# 18_-SP3_PMIC_BLOCK.net
KiCad netlist of a schematic drawn in Altium Designer
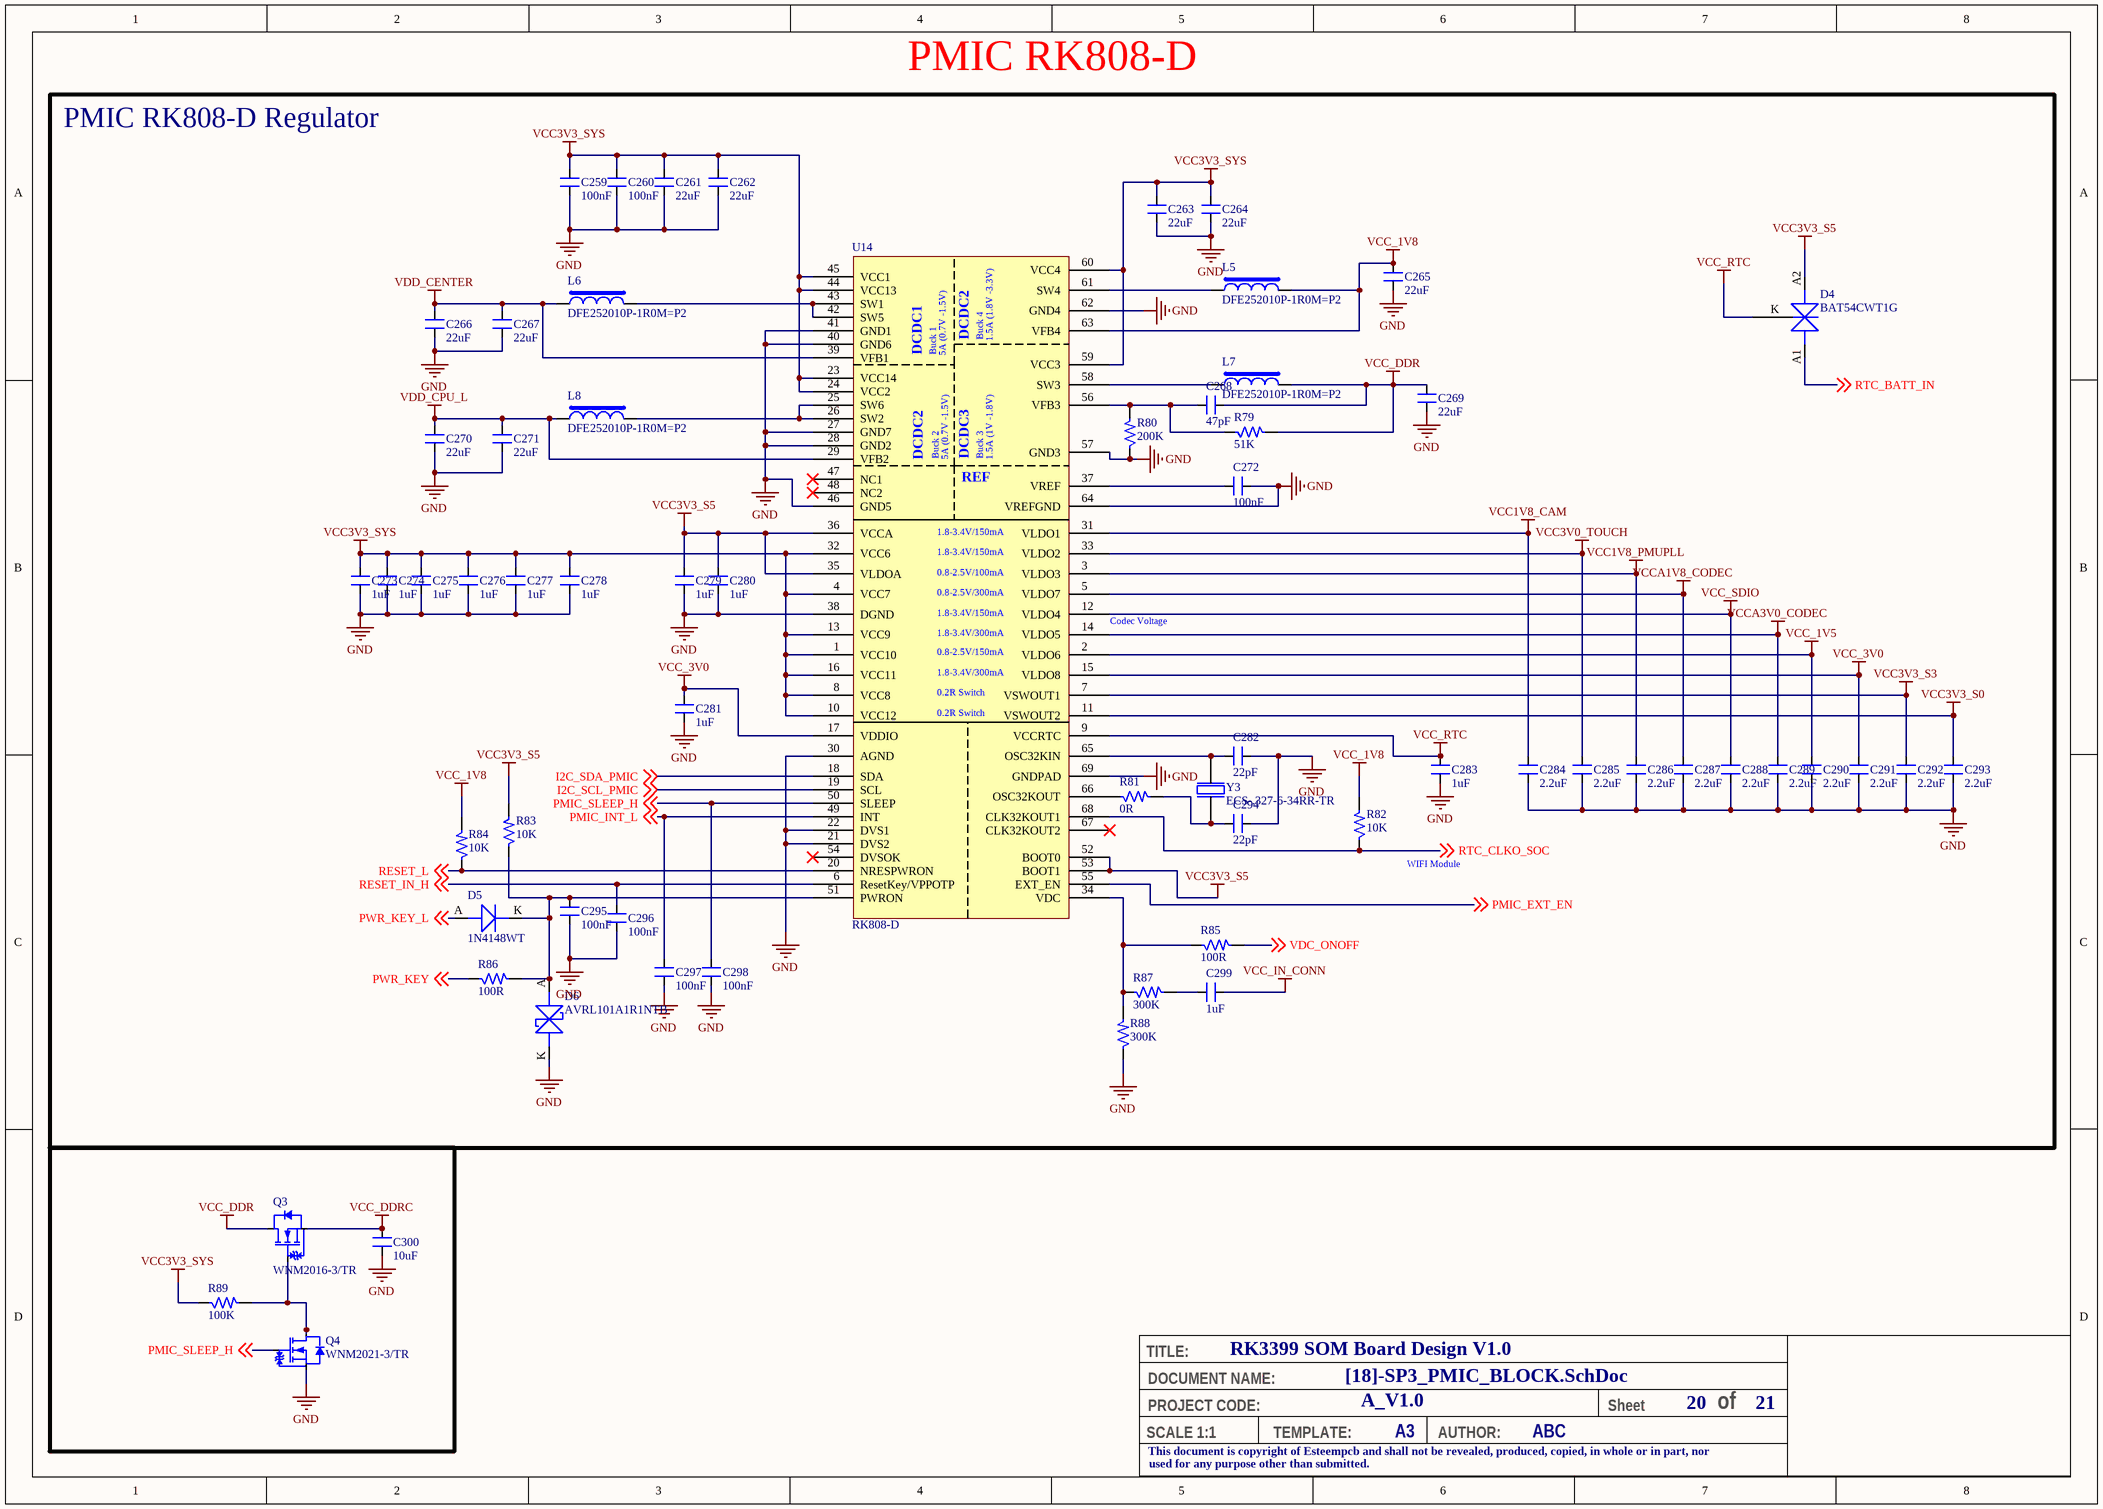
[diagram p0: [18]-SP3_PMIC_BLOCK.SchDoc]

(export (version "E")
  (design (tool "Eeschema 10.0.6"))
  (components
    (comp (ref "C259")
      (value "100nF")
      (footprint "CAP_0402")
      (description "0.1µF ±10% 25V Ceramic Capacitor X7R 0402 (1005 Metric)")
      (fields
        (field (name "MANUFACTURER") "Walsin Technology Corporation")
        (field (name "MANUFACTURER PART NUMBER") "0402B104K250CT")
      )
      (libsource (lib "RK3399 _Module_Schlib") (part "CAP_100nF-25V-10%-0402"))
    )
    (comp (ref "C260")
      (value "100nF")
      (footprint "CAP_0402")
      (description "0.1µF ±10% 25V Ceramic Capacitor X7R 0402 (1005 Metric)")
      (fields
        (field (name "MANUFACTURER") "Walsin Technology Corporation")
        (field (name "MANUFACTURER PART NUMBER") "0402B104K250CT")
      )
      (libsource (lib "RK3399 _Module_Schlib") (part "CAP_100nF-25V-10%-0402"))
    )
    (comp (ref "C261")
      (value "22uF")
      (footprint "CAP_0603")
      (description "22µF ±20% 10V Ceramic Capacitor X5R 0603 (1608 Metric)")
      (fields
        (field (name "MANUFACTURER") "Murata Electronics")
        (field (name "MANUFACTURER PART NUMBER") "GRM188R61A226ME15D")
      )
      (libsource (lib "RK3399 _Module_Schlib") (part "CAP_22uF-10V-20%-0603"))
    )
    (comp (ref "C262")
      (value "22uF")
      (footprint "CAP_0603")
      (description "22µF ±20% 10V Ceramic Capacitor X5R 0603 (1608 Metric)")
      (fields
        (field (name "MANUFACTURER") "Murata Electronics")
        (field (name "MANUFACTURER PART NUMBER") "GRM188R61A226ME15D")
      )
      (libsource (lib "RK3399 _Module_Schlib") (part "CAP_22uF-10V-20%-0603"))
    )
    (comp (ref "C263")
      (value "22uF")
      (footprint "CAP_0603")
      (description "22µF ±20% 10V Ceramic Capacitor X5R 0603 (1608 Metric)")
      (fields
        (field (name "MANUFACTURER") "Murata Electronics")
        (field (name "MANUFACTURER PART NUMBER") "GRM188R61A226ME15D")
      )
      (libsource (lib "RK3399 _Module_Schlib") (part "CAP_22uF-10V-20%-0603"))
    )
    (comp (ref "C264")
      (value "22uF")
      (footprint "CAP_0603")
      (description "22µF ±20% 10V Ceramic Capacitor X5R 0603 (1608 Metric)")
      (fields
        (field (name "MANUFACTURER") "Murata Electronics")
        (field (name "MANUFACTURER PART NUMBER") "GRM188R61A226ME15D")
      )
      (libsource (lib "RK3399 _Module_Schlib") (part "CAP_22uF-10V-20%-0603"))
    )
    (comp (ref "C265")
      (value "22uF")
      (footprint "CAP_0603")
      (description "22µF ±20% 10V Ceramic Capacitor X5R 0603 (1608 Metric)")
      (fields
        (field (name "MANUFACTURER") "Murata Electronics")
        (field (name "MANUFACTURER PART NUMBER") "GRM188R61A226ME15D")
      )
      (libsource (lib "RK3399 _Module_Schlib") (part "CAP_22uF-10V-20%-0603"))
    )
    (comp (ref "C266")
      (value "22uF")
      (footprint "CAP_0603")
      (description "22µF ±20% 10V Ceramic Capacitor X5R 0603 (1608 Metric)")
      (fields
        (field (name "MANUFACTURER") "Murata Electronics")
        (field (name "MANUFACTURER PART NUMBER") "GRM188R61A226ME15D")
      )
      (libsource (lib "RK3399 _Module_Schlib") (part "CAP_22uF-10V-20%-0603"))
    )
    (comp (ref "C267")
      (value "22uF")
      (footprint "CAP_0603")
      (description "22µF ±20% 10V Ceramic Capacitor X5R 0603 (1608 Metric)")
      (fields
        (field (name "MANUFACTURER") "Murata Electronics")
        (field (name "MANUFACTURER PART NUMBER") "GRM188R61A226ME15D")
      )
      (libsource (lib "RK3399 _Module_Schlib") (part "CAP_22uF-10V-20%-0603"))
    )
    (comp (ref "C268")
      (value "47pF")
      (footprint "CAP_0402")
      (description "47pF ±10% 10V Ceramic Capacitor C0G, NP0 0402 (1005 Metric)")
      (fields
        (field (name "MANUFACTURER") "KEMET")
        (field (name "MANUFACTURER PART NUMBER") "C0402C470K8GAC7867")
      )
      (libsource (lib "RK3399 _Module_Schlib") (part "CAP_47pF-10V-10%-0402"))
    )
    (comp (ref "C269")
      (value "22uF")
      (footprint "CAP_0603")
      (description "22µF ±20% 10V Ceramic Capacitor X5R 0603 (1608 Metric)")
      (fields
        (field (name "MANUFACTURER") "Murata Electronics")
        (field (name "MANUFACTURER PART NUMBER") "GRM188R61A226ME15D")
      )
      (libsource (lib "RK3399 _Module_Schlib") (part "CAP_22uF-10V-20%-0603"))
    )
    (comp (ref "C270")
      (value "22uF")
      (footprint "CAP_0603")
      (description "22µF ±20% 10V Ceramic Capacitor X5R 0603 (1608 Metric)")
      (fields
        (field (name "MANUFACTURER") "Murata Electronics")
        (field (name "MANUFACTURER PART NUMBER") "GRM188R61A226ME15D")
      )
      (libsource (lib "RK3399 _Module_Schlib") (part "CAP_22uF-10V-20%-0603"))
    )
    (comp (ref "C271")
      (value "22uF")
      (footprint "CAP_0603")
      (description "22µF ±20% 10V Ceramic Capacitor X5R 0603 (1608 Metric)")
      (fields
        (field (name "MANUFACTURER") "Murata Electronics")
        (field (name "MANUFACTURER PART NUMBER") "GRM188R61A226ME15D")
      )
      (libsource (lib "RK3399 _Module_Schlib") (part "CAP_22uF-10V-20%-0603"))
    )
    (comp (ref "C272")
      (value "100nF")
      (footprint "CAP_0402")
      (description "0.1µF ±10% 25V Ceramic Capacitor X7R 0402 (1005 Metric)")
      (fields
        (field (name "MANUFACTURER") "Walsin Technology Corporation")
        (field (name "MANUFACTURER PART NUMBER") "0402B104K250CT")
      )
      (libsource (lib "RK3399 _Module_Schlib") (part "CAP_100nF-25V-10%-0402"))
    )
    (comp (ref "C273")
      (value "1uF")
      (footprint "CAP_0402")
      (description "1µF ±10% 16V Ceramic Capacitor X5R 0402 (1005 Metric)")
      (fields
        (field (name "MANUFACTURER") "Knowles Novacap")
        (field (name "MANUFACTURER PART NUMBER") "0402BW105K160YT")
      )
      (libsource (lib "RK3399 _Module_Schlib") (part "CAP_1uF-16V-10%-0402"))
    )
    (comp (ref "C274")
      (value "1uF")
      (footprint "CAP_0402")
      (description "1µF ±10% 16V Ceramic Capacitor X5R 0402 (1005 Metric)")
      (fields
        (field (name "MANUFACTURER") "Knowles Novacap")
        (field (name "MANUFACTURER PART NUMBER") "0402BW105K160YT")
      )
      (libsource (lib "RK3399 _Module_Schlib") (part "CAP_1uF-16V-10%-0402"))
    )
    (comp (ref "C275")
      (value "1uF")
      (footprint "CAP_0402")
      (description "1µF ±10% 16V Ceramic Capacitor X5R 0402 (1005 Metric)")
      (fields
        (field (name "MANUFACTURER") "Knowles Novacap")
        (field (name "MANUFACTURER PART NUMBER") "0402BW105K160YT")
      )
      (libsource (lib "RK3399 _Module_Schlib") (part "CAP_1uF-16V-10%-0402"))
    )
    (comp (ref "C276")
      (value "1uF")
      (footprint "CAP_0402")
      (description "1µF ±10% 16V Ceramic Capacitor X5R 0402 (1005 Metric)")
      (fields
        (field (name "MANUFACTURER") "Knowles Novacap")
        (field (name "MANUFACTURER PART NUMBER") "0402BW105K160YT")
      )
      (libsource (lib "RK3399 _Module_Schlib") (part "CAP_1uF-16V-10%-0402"))
    )
    (comp (ref "C277")
      (value "1uF")
      (footprint "CAP_0402")
      (description "1µF ±10% 16V Ceramic Capacitor X5R 0402 (1005 Metric)")
      (fields
        (field (name "MANUFACTURER") "Knowles Novacap")
        (field (name "MANUFACTURER PART NUMBER") "0402BW105K160YT")
      )
      (libsource (lib "RK3399 _Module_Schlib") (part "CAP_1uF-16V-10%-0402"))
    )
    (comp (ref "C278")
      (value "1uF")
      (footprint "CAP_0402")
      (description "1µF ±10% 16V Ceramic Capacitor X5R 0402 (1005 Metric)")
      (fields
        (field (name "MANUFACTURER") "Knowles Novacap")
        (field (name "MANUFACTURER PART NUMBER") "0402BW105K160YT")
      )
      (libsource (lib "RK3399 _Module_Schlib") (part "CAP_1uF-16V-10%-0402"))
    )
    (comp (ref "C279")
      (value "1uF")
      (footprint "CAP_0402")
      (description "1µF ±10% 16V Ceramic Capacitor X5R 0402 (1005 Metric)")
      (fields
        (field (name "MANUFACTURER") "Knowles Novacap")
        (field (name "MANUFACTURER PART NUMBER") "0402BW105K160YT")
      )
      (libsource (lib "RK3399 _Module_Schlib") (part "CAP_1uF-16V-10%-0402"))
    )
    (comp (ref "C280")
      (value "1uF")
      (footprint "CAP_0402")
      (description "1µF ±10% 16V Ceramic Capacitor X5R 0402 (1005 Metric)")
      (fields
        (field (name "MANUFACTURER") "Knowles Novacap")
        (field (name "MANUFACTURER PART NUMBER") "0402BW105K160YT")
      )
      (libsource (lib "RK3399 _Module_Schlib") (part "CAP_1uF-16V-10%-0402"))
    )
    (comp (ref "C281")
      (value "1uF")
      (footprint "CAP_0402")
      (description "1µF ±10% 16V Ceramic Capacitor X5R 0402 (1005 Metric)")
      (fields
        (field (name "MANUFACTURER") "Knowles Novacap")
        (field (name "MANUFACTURER PART NUMBER") "0402BW105K160YT")
      )
      (libsource (lib "RK3399 _Module_Schlib") (part "CAP_1uF-16V-10%-0402"))
    )
    (comp (ref "C282")
      (value "22pF")
      (footprint "CAP_0402")
      (description "22pF ±10% 10V Ceramic Capacitor C0G, NP0 0402 (1005 Metric)")
      (fields
        (field (name "MANUFACTURER") "KEMET")
        (field (name "MANUFACTURER PART NUMBER") "C0402C220K8GACTU")
      )
      (libsource (lib "RK3399 _Module_Schlib") (part "CAP_22pF-10V-10%-0402"))
    )
    (comp (ref "C283")
      (value "1uF")
      (footprint "CAP_0402")
      (description "1µF ±10% 16V Ceramic Capacitor X5R 0402 (1005 Metric)")
      (fields
        (field (name "MANUFACTURER") "Knowles Novacap")
        (field (name "MANUFACTURER PART NUMBER") "0402BW105K160YT")
      )
      (libsource (lib "RK3399 _Module_Schlib") (part "CAP_1uF-16V-10%-0402"))
    )
    (comp (ref "C284")
      (value "2.2uF")
      (footprint "CAP_0402")
      (description "2.2µF ±10% 10V Ceramic Capacitor X5R 0402 (1005 Metric)")
      (fields
        (field (name "MANUFACTURER") "Murata Electronics")
        (field (name "MANUFACTURER PART NUMBER") "GRM155R61A225KE95D")
      )
      (libsource (lib "RK3399 _Module_Schlib") (part "CAP_2.2uF-10V-10%-0402"))
    )
    (comp (ref "C285")
      (value "2.2uF")
      (footprint "CAP_0402")
      (description "2.2µF ±10% 10V Ceramic Capacitor X5R 0402 (1005 Metric)")
      (fields
        (field (name "MANUFACTURER") "Murata Electronics")
        (field (name "MANUFACTURER PART NUMBER") "GRM155R61A225KE95D")
      )
      (libsource (lib "RK3399 _Module_Schlib") (part "CAP_2.2uF-10V-10%-0402"))
    )
    (comp (ref "C286")
      (value "2.2uF")
      (footprint "CAP_0402")
      (description "2.2µF ±10% 10V Ceramic Capacitor X5R 0402 (1005 Metric)")
      (fields
        (field (name "MANUFACTURER") "Murata Electronics")
        (field (name "MANUFACTURER PART NUMBER") "GRM155R61A225KE95D")
      )
      (libsource (lib "RK3399 _Module_Schlib") (part "CAP_2.2uF-10V-10%-0402"))
    )
    (comp (ref "C287")
      (value "2.2uF")
      (footprint "CAP_0402")
      (description "2.2µF ±10% 10V Ceramic Capacitor X5R 0402 (1005 Metric)")
      (fields
        (field (name "MANUFACTURER") "Murata Electronics")
        (field (name "MANUFACTURER PART NUMBER") "GRM155R61A225KE95D")
      )
      (libsource (lib "RK3399 _Module_Schlib") (part "CAP_2.2uF-10V-10%-0402"))
    )
    (comp (ref "C288")
      (value "2.2uF")
      (footprint "CAP_0402")
      (description "2.2µF ±10% 10V Ceramic Capacitor X5R 0402 (1005 Metric)")
      (fields
        (field (name "MANUFACTURER") "Murata Electronics")
        (field (name "MANUFACTURER PART NUMBER") "GRM155R61A225KE95D")
      )
      (libsource (lib "RK3399 _Module_Schlib") (part "CAP_2.2uF-10V-10%-0402"))
    )
    (comp (ref "C289")
      (value "2.2uF")
      (footprint "CAP_0402")
      (description "2.2µF ±10% 10V Ceramic Capacitor X5R 0402 (1005 Metric)")
      (fields
        (field (name "MANUFACTURER") "Murata Electronics")
        (field (name "MANUFACTURER PART NUMBER") "GRM155R61A225KE95D")
      )
      (libsource (lib "RK3399 _Module_Schlib") (part "CAP_2.2uF-10V-10%-0402"))
    )
    (comp (ref "C290")
      (value "2.2uF")
      (footprint "CAP_0402")
      (description "2.2µF ±10% 10V Ceramic Capacitor X5R 0402 (1005 Metric)")
      (fields
        (field (name "MANUFACTURER") "Murata Electronics")
        (field (name "MANUFACTURER PART NUMBER") "GRM155R61A225KE95D")
      )
      (libsource (lib "RK3399 _Module_Schlib") (part "CAP_2.2uF-10V-10%-0402"))
    )
    (comp (ref "C291")
      (value "2.2uF")
      (footprint "CAP_0402")
      (description "2.2µF ±10% 10V Ceramic Capacitor X5R 0402 (1005 Metric)")
      (fields
        (field (name "MANUFACTURER") "Murata Electronics")
        (field (name "MANUFACTURER PART NUMBER") "GRM155R61A225KE95D")
      )
      (libsource (lib "RK3399 _Module_Schlib") (part "CAP_2.2uF-10V-10%-0402"))
    )
    (comp (ref "C292")
      (value "2.2uF")
      (footprint "CAP_0402")
      (description "2.2µF ±10% 10V Ceramic Capacitor X5R 0402 (1005 Metric)")
      (fields
        (field (name "MANUFACTURER") "Murata Electronics")
        (field (name "MANUFACTURER PART NUMBER") "GRM155R61A225KE95D")
      )
      (libsource (lib "RK3399 _Module_Schlib") (part "CAP_2.2uF-10V-10%-0402"))
    )
    (comp (ref "C293")
      (value "2.2uF")
      (footprint "CAP_0402")
      (description "2.2µF ±10% 10V Ceramic Capacitor X5R 0402 (1005 Metric)")
      (fields
        (field (name "MANUFACTURER") "Murata Electronics")
        (field (name "MANUFACTURER PART NUMBER") "GRM155R61A225KE95D")
      )
      (libsource (lib "RK3399 _Module_Schlib") (part "CAP_2.2uF-10V-10%-0402"))
    )
    (comp (ref "C294")
      (value "22pF")
      (footprint "CAP_0402")
      (description "22pF ±10% 10V Ceramic Capacitor C0G, NP0 0402 (1005 Metric)")
      (fields
        (field (name "MANUFACTURER") "KEMET")
        (field (name "MANUFACTURER PART NUMBER") "C0402C220K8GACTU")
      )
      (libsource (lib "RK3399 _Module_Schlib") (part "CAP_22pF-10V-10%-0402"))
    )
    (comp (ref "C295")
      (value "100nF")
      (footprint "CAP_0402")
      (description "0.1µF ±10% 25V Ceramic Capacitor X7R 0402 (1005 Metric)")
      (fields
        (field (name "MANUFACTURER") "Walsin Technology Corporation")
        (field (name "MANUFACTURER PART NUMBER") "0402B104K250CT")
      )
      (libsource (lib "RK3399 _Module_Schlib") (part "CAP_100nF-25V-10%-0402"))
    )
    (comp (ref "C296")
      (value "100nF")
      (footprint "CAP_0402")
      (description "0.1µF ±10% 25V Ceramic Capacitor X7R 0402 (1005 Metric)")
      (fields
        (field (name "MANUFACTURER") "Walsin Technology Corporation")
        (field (name "MANUFACTURER PART NUMBER") "0402B104K250CT")
      )
      (libsource (lib "RK3399 _Module_Schlib") (part "CAP_100nF-25V-10%-0402"))
    )
    (comp (ref "C297")
      (value "100nF")
      (footprint "CAP_0402")
      (description "0.1µF ±10% 25V Ceramic Capacitor X7R 0402 (1005 Metric)")
      (fields
        (field (name "MANUFACTURER") "Walsin Technology Corporation")
        (field (name "MANUFACTURER PART NUMBER") "0402B104K250CT")
      )
      (libsource (lib "RK3399 _Module_Schlib") (part "CAP_100nF-25V-10%-0402"))
    )
    (comp (ref "C298")
      (value "100nF")
      (footprint "CAP_0402")
      (description "0.1µF ±10% 25V Ceramic Capacitor X7R 0402 (1005 Metric)")
      (fields
        (field (name "MANUFACTURER") "Walsin Technology Corporation")
        (field (name "MANUFACTURER PART NUMBER") "0402B104K250CT")
      )
      (libsource (lib "RK3399 _Module_Schlib") (part "CAP_100nF-25V-10%-0402"))
    )
    (comp (ref "C299")
      (value "1uF")
      (footprint "CAP_0402")
      (description "1µF ±10% 16V Ceramic Capacitor X5R 0402 (1005 Metric)")
      (fields
        (field (name "MANUFACTURER") "Knowles Novacap")
        (field (name "MANUFACTURER PART NUMBER") "0402BW105K160YT")
      )
      (libsource (lib "RK3399 _Module_Schlib") (part "CAP_1uF-16V-10%-0402"))
    )
    (comp (ref "C300")
      (value "10uF")
      (footprint "CAP_0402")
      (description "10µF ±20% 10V Ceramic Capacitor X5R 0402 (1005 Metric)")
      (fields
        (field (name "MANUFACTURER PART NUMBER") "CL05A106MP5NUNC")
        (field (name "MANUFACTURER") "Samsung Electro-Mechanics")
      )
      (libsource (lib "RK3399 _Module_Schlib") (part "CAP_10uF-10V-20%-0402"))
    )
    (comp (ref "D4")
      (value "BAT54CWT1G")
      (footprint "DIO_SOT-323-3")
      (description "Diode Array 1 Pair Common Cathode Schottky 30V 200mA (DC) Surface Mount SC-70, SOT-323")
      (fields (field (name "MANUFACTURER") "ON Semiconductor"))
      (libsource (lib "RK3399 _Module_Schlib") (part "DIO-S-A_30V-200mA-SOT-323"))
    )
    (comp (ref "D5")
      (value "1N4148WT")
      (footprint "DIO_SOD523")
      (description "Diode Standard 100V 300mA (DC) Surface Mount SOD-123")
      (fields (field (name "MANUFACTURER") "FAIRCHILD"))
      (libsource (lib "RK3399 _Module_Schlib") (part "DIO_75V-200mA-SOD-523F"))
    )
    (comp (ref "D6")
      (value "AVRL101A1R1NTB")
      (footprint "DIO_0402_SMD")
      (description "39V Varistor 1 Circuit Surface Mount, MLCV 0402 (1005 Metric)")
      (fields (field (name "MANUFACTURER") "TDK Corporation"))
      (libsource (lib "RK3399 _Module_Schlib") (part "DIO-T_10V-39V-0402"))
    )
    (comp (ref "L5")
      (value "DFE252010P-1R0M=P2")
      (footprint "IND_1008")
      (description "1µH Shielded Wirewound Inductor 3.8A 54mOhm Max 1008 (2520 Metric)")
      (fields (field (name "MANUFACTURER") "Murata Electronics"))
      (libsource (lib "RK3399 _Module_Schlib") (part "IND_1uH-3.8A-20%-1008"))
    )
    (comp (ref "L6")
      (value "DFE252010P-1R0M=P2")
      (footprint "IND_1008")
      (description "1µH Shielded Wirewound Inductor 3.8A 54mOhm Max 1008 (2520 Metric)")
      (fields (field (name "MANUFACTURER") "Murata Electronics"))
      (libsource (lib "RK3399 _Module_Schlib") (part "IND_1uH-3.8A-20%-1008"))
    )
    (comp (ref "L7")
      (value "DFE252010P-1R0M=P2")
      (footprint "IND_1008")
      (description "1µH Shielded Wirewound Inductor 3.8A 54mOhm Max 1008 (2520 Metric)")
      (fields (field (name "MANUFACTURER") "Murata Electronics"))
      (libsource (lib "RK3399 _Module_Schlib") (part "IND_1uH-3.8A-20%-1008"))
    )
    (comp (ref "L8")
      (value "DFE252010P-1R0M=P2")
      (footprint "IND_1008")
      (description "1µH Shielded Wirewound Inductor 3.8A 54mOhm Max 1008 (2520 Metric)")
      (fields (field (name "MANUFACTURER") "Murata Electronics"))
      (libsource (lib "RK3399 _Module_Schlib") (part "IND_1uH-3.8A-20%-1008"))
    )
    (comp (ref "Q3")
      (value "WNM2016-3/TR")
      (footprint "SOT 23-3")
      (description "N Channel 20V 2.9A 1V @ 250uA 47mΩ @ 3.6A,4.5V 700mW SOT-23(SOT-23-3) MOSFET RoHS")
      (fields (field (name "MANUFACTURER") "WILLSEMI(Will Semicon)"))
      (libsource (lib "RK3399 _Module_Schlib") (part "MOSFET-N_20V-2.9A-SOT-23"))
    )
    (comp (ref "Q4")
      (value "WNM2021-3/TR")
      (footprint "SOT-323-3")
      (description "N Channel 20V 820mA 850mV @ 250uA 310mΩ @ 550mA,4.5V 310mW SOT-323(SC-70) MOSFET RoHS")
      (fields (field (name "MANUFACTURER") "WILLSEMI(Will Semicon)"))
      (libsource (lib "RK3399 _Module_Schlib") (part "MOSFET-N_20V-820mA-SOT-323"))
    )
    (comp (ref "R79")
      (value "51K")
      (footprint "RES_0402")
      (description "51 kOhms ±1% 0.1W, 1/10W Chip Resistor 0402 (1005 Metric) Automotive AEC-Q200 Thick Film")
      (fields
        (field (name "MANUFACTURER") "Panasonic Electronic Components")
        (field (name "MANUFACTURER PART NUMBER") "ERJ-2RKF5102X")
      )
      (libsource (lib "RK3399 _Module_Schlib") (part "RES_51K-0.1W-1%-0402"))
    )
    (comp (ref "R80")
      (value "200K")
      (footprint "RES_0402")
      (description "200 kOhms ±1% 0.1W, 1/10W Chip Resistor 0402 (1005 Metric) Automotive AEC-Q200 Thick Film")
      (fields
        (field (name "MANUFACTURER") "Panasonic Electronic Components")
        (field (name "MANUFACTURER PART NUMBER") "ERJ-2RKF2003X")
      )
      (libsource (lib "RK3399 _Module_Schlib") (part "RES_200K-0.1W-1%-0402"))
    )
    (comp (ref "R81")
      (value "0R")
      (footprint "RES_0402")
      (description "0 Ohms Jumper 0.1W, 1/10W Chip Resistor 0402 (1005 Metric) Automotive AEC-Q200 Thick Film")
      (fields
        (field (name "MANUFACTURER") "Panasonic Electronic Components")
        (field (name "MANUFACTURER PART NUMBER") "ERJ-2GE0R00X")
      )
      (libsource (lib "RK3399 _Module_Schlib") (part "RES_0R-0.1W-1%-0402"))
    )
    (comp (ref "R82")
      (value "10K")
      (footprint "RES_0402")
      (description "10 kOhms ±1% 0.1W, 1/10W Chip Resistor 0402 (1005 Metric) Anti-Sulfur Thin Film")
      (fields
        (field (name "MANUFACTURER") "Vishay Beyschlag/Draloric/BC Components")
        (field (name "MANUFACTURER PART NUMBER") "MCS04020C1002FE000")
      )
      (libsource (lib "RK3399 _Module_Schlib") (part "RES_10K-0.1W-1%-0402"))
    )
    (comp (ref "R83")
      (value "10K")
      (footprint "RES_0402")
      (description "10 kOhms ±1% 0.1W, 1/10W Chip Resistor 0402 (1005 Metric) Anti-Sulfur Thin Film")
      (fields
        (field (name "MANUFACTURER") "Vishay Beyschlag/Draloric/BC Components")
        (field (name "MANUFACTURER PART NUMBER") "MCS04020C1002FE000")
      )
      (libsource (lib "RK3399 _Module_Schlib") (part "RES_10K-0.1W-1%-0402"))
    )
    (comp (ref "R84")
      (value "10K")
      (footprint "RES_0402")
      (description "10 kOhms ±1% 0.1W, 1/10W Chip Resistor 0402 (1005 Metric) Anti-Sulfur Thin Film")
      (fields
        (field (name "MANUFACTURER") "Vishay Beyschlag/Draloric/BC Components")
        (field (name "MANUFACTURER PART NUMBER") "MCS04020C1002FE000")
      )
      (libsource (lib "RK3399 _Module_Schlib") (part "RES_10K-0.1W-1%-0402"))
    )
    (comp (ref "R85")
      (value "100R")
      (footprint "RES_0402")
      (fields
        (field (name "MANUFACTURER") "KOA Speer Electronics, Inc.")
        (field (name "MANUFACTURER PART NUMBER") "RK73H1ETTP1000F")
      )
      (libsource (lib "RK3399 _Module_Schlib") (part "RES_100R-0.1W-1%-0402"))
    )
    (comp (ref "R86")
      (value "100R")
      (footprint "RES_0402")
      (fields
        (field (name "MANUFACTURER") "KOA Speer Electronics, Inc.")
        (field (name "MANUFACTURER PART NUMBER") "RK73H1ETTP1000F")
      )
      (libsource (lib "RK3399 _Module_Schlib") (part "RES_100R-0.1W-1%-0402"))
    )
    (comp (ref "R87")
      (value "300K")
      (footprint "RES_0402")
      (description "300 kOhms ±1% 0.1W, 1/10W Chip Resistor 0402 (1005 Metric) Automotive AEC-Q200 Thick Film")
      (fields
        (field (name "MANUFACTURER") "Panasonic Electronic Components")
        (field (name "MANUFACTURER PART NUMBER") "ERJ-2RKF3003X")
      )
      (libsource (lib "RK3399 _Module_Schlib") (part "RES_300K-0.1W-1%-0402"))
    )
    (comp (ref "R88")
      (value "300K")
      (footprint "RES_0402")
      (description "300 kOhms ±1% 0.1W, 1/10W Chip Resistor 0402 (1005 Metric) Automotive AEC-Q200 Thick Film")
      (fields
        (field (name "MANUFACTURER") "Panasonic Electronic Components")
        (field (name "MANUFACTURER PART NUMBER") "ERJ-2RKF3003X")
      )
      (libsource (lib "RK3399 _Module_Schlib") (part "RES_300K-0.1W-1%-0402"))
    )
    (comp (ref "R89")
      (value "100K")
      (footprint "RES_0402")
      (description "100 kOhms ±1% 0.1W, 1/10W Chip Resistor 0402 (1005 Metric) Anti-Sulfur Thin Film")
      (fields
        (field (name "MANUFACTURER") "Vishay Beyschlag/Draloric/BC Components")
        (field (name "MANUFACTURER PART NUMBER") "MCS04020C1003FE000")
      )
      (libsource (lib "RK3399 _Module_Schlib") (part "RES_100K-0.1W-1%-0402"))
    )
    (comp (ref "U14")
      (value "RK808-D")
      (footprint "QFN68_13.7_220.4X220.4_SMD")
      (description "The RK808 is a complete power supply solution for Portable systems.")
      (fields (field (name "MANUFACTURER") "Rockchip"))
      (libsource (lib "RK3399 _Module_Schlib") (part "IC_RK808-D-QFN68"))
    )
    (comp (ref "Y3")
      (value "ECS-.327-6-34RR-TR")
      (footprint "XTAL_ECS-.327-6-34RR-TR")
      (description "32.768kHz ±20ppm Crystal 12pF 80 kOhms 2-SMD, No Lead")
      (fields (field (name "MANUFACTURER") "Ecliptek"))
      (libsource (lib "RK3399 _Module_Schlib") (part "XTAL_32.768Khz-22pF-SMD"))
    )
  )
  (nets
    (net (code "1") (name "GND") (class "Default")
      (node (ref "C259") (pin "1") (pinfunction "1_1") (pintype "passive"))
      (node (ref "C260") (pin "1") (pinfunction "1_1") (pintype "passive"))
      (node (ref "C261") (pin "1") (pinfunction "1_1") (pintype "passive"))
      (node (ref "C262") (pin "1") (pinfunction "1_1") (pintype "passive"))
      (node (ref "C263") (pin "1") (pinfunction "1_1") (pintype "passive"))
      (node (ref "C264") (pin "1") (pinfunction "1_1") (pintype "passive"))
      (node (ref "C265") (pin "1") (pinfunction "1_1") (pintype "passive"))
      (node (ref "C266") (pin "1") (pinfunction "1_1") (pintype "passive"))
      (node (ref "C267") (pin "1") (pinfunction "1_1") (pintype "passive"))
      (node (ref "C269") (pin "1") (pinfunction "1_1") (pintype "passive"))
      (node (ref "C270") (pin "1") (pinfunction "1_1") (pintype "passive"))
      (node (ref "C271") (pin "1") (pinfunction "1_1") (pintype "passive"))
      (node (ref "C272") (pin "1") (pinfunction "1_1") (pintype "passive"))
      (node (ref "C273") (pin "2") (pinfunction "2_2") (pintype "passive"))
      (node (ref "C274") (pin "1") (pinfunction "1_1") (pintype "passive"))
      (node (ref "C275") (pin "1") (pinfunction "1_1") (pintype "passive"))
      (node (ref "C276") (pin "1") (pinfunction "1_1") (pintype "passive"))
      (node (ref "C277") (pin "1") (pinfunction "1_1") (pintype "passive"))
      (node (ref "C278") (pin "1") (pinfunction "1_1") (pintype "passive"))
      (node (ref "C279") (pin "1") (pinfunction "1_1") (pintype "passive"))
      (node (ref "C280") (pin "1") (pinfunction "1_1") (pintype "passive"))
      (node (ref "C281") (pin "1") (pinfunction "1_1") (pintype "passive"))
      (node (ref "C282") (pin "2") (pinfunction "2_2") (pintype "passive"))
      (node (ref "C283") (pin "1") (pinfunction "1_1") (pintype "passive"))
      (node (ref "C284") (pin "1") (pinfunction "1_1") (pintype "passive"))
      (node (ref "C285") (pin "1") (pinfunction "1_1") (pintype "passive"))
      (node (ref "C286") (pin "1") (pinfunction "1_1") (pintype "passive"))
      (node (ref "C287") (pin "1") (pinfunction "1_1") (pintype "passive"))
      (node (ref "C288") (pin "1") (pinfunction "1_1") (pintype "passive"))
      (node (ref "C289") (pin "1") (pinfunction "1_1") (pintype "passive"))
      (node (ref "C290") (pin "1") (pinfunction "1_1") (pintype "passive"))
      (node (ref "C291") (pin "1") (pinfunction "1_1") (pintype "passive"))
      (node (ref "C292") (pin "1") (pinfunction "1_1") (pintype "passive"))
      (node (ref "C293") (pin "1") (pinfunction "1_1") (pintype "passive"))
      (node (ref "C294") (pin "2") (pinfunction "2_2") (pintype "passive"))
      (node (ref "C295") (pin "1") (pinfunction "1_1") (pintype "passive"))
      (node (ref "C296") (pin "1") (pinfunction "1_1") (pintype "passive"))
      (node (ref "C297") (pin "1") (pinfunction "1_1") (pintype "passive"))
      (node (ref "C298") (pin "1") (pinfunction "1_1") (pintype "passive"))
      (node (ref "C300") (pin "1") (pinfunction "1_1") (pintype "passive"))
      (node (ref "D6") (pin "K") (pinfunction "K_K") (pintype "passive"))
      (node (ref "Q4") (pin "2") (pinfunction "S_2") (pintype "passive"))
      (node (ref "R80") (pin "1") (pinfunction "1_1") (pintype "passive"))
      (node (ref "R88") (pin "1") (pinfunction "1_1") (pintype "passive"))
      (node (ref "U14") (pin "21") (pinfunction "DVS2_21") (pintype "passive"))
      (node (ref "U14") (pin "22") (pinfunction "DVS1_22") (pintype "passive"))
      (node (ref "U14") (pin "27") (pinfunction "GND7_27") (pintype "passive"))
      (node (ref "U14") (pin "28") (pinfunction "GND2_28") (pintype "passive"))
      (node (ref "U14") (pin "30") (pinfunction "AGND_30") (pintype "passive"))
      (node (ref "U14") (pin "38") (pinfunction "DGND_38") (pintype "passive"))
      (node (ref "U14") (pin "40") (pinfunction "GND6_40") (pintype "passive"))
      (node (ref "U14") (pin "41") (pinfunction "GND1_41") (pintype "passive"))
      (node (ref "U14") (pin "46") (pinfunction "GND5_46") (pintype "passive"))
      (node (ref "U14") (pin "57") (pinfunction "GND3_57") (pintype "passive"))
      (node (ref "U14") (pin "62") (pinfunction "GND4_62") (pintype "passive"))
      (node (ref "U14") (pin "64") (pinfunction "VREFGND_64") (pintype "passive"))
      (node (ref "U14") (pin "69") (pinfunction "GNDPAD_69") (pintype "passive"))
    )
    (net (code "2") (name "I2C_SCL_PMIC") (class "Default")
      (node (ref "U14") (pin "19") (pinfunction "SCL_19") (pintype "passive"))
    )
    (net (code "3") (name "I2C_SDA_PMIC") (class "Default")
      (node (ref "U14") (pin "18") (pinfunction "SDA_18") (pintype "passive"))
    )
    (net (code "4") (name "Net-(C294-Pad1)") (class "Default")
      (node (ref "C294") (pin "1") (pinfunction "1_1") (pintype "passive"))
      (node (ref "R81") (pin "2") (pinfunction "2_2") (pintype "passive"))
      (node (ref "Y3") (pin "1") (pinfunction "1_1") (pintype "passive"))
    )
    (net (code "5") (name "Net-(C299-Pad2)") (class "Default")
      (node (ref "C299") (pin "2") (pinfunction "2_2") (pintype "passive"))
      (node (ref "R87") (pin "2") (pinfunction "2_2") (pintype "passive"))
    )
    (net (code "6") (name "Net-(D5-CATHODE)") (class "Default")
      (node (ref "C295") (pin "2") (pinfunction "2_2") (pintype "passive"))
      (node (ref "D5") (pin "K") (pinfunction "CATHODE_K") (pintype "passive"))
      (node (ref "D6") (pin "A") (pinfunction "A_A") (pintype "passive"))
      (node (ref "R83") (pin "1") (pinfunction "1_1") (pintype "passive"))
      (node (ref "R86") (pin "2") (pinfunction "2_2") (pintype "passive"))
      (node (ref "U14") (pin "51") (pinfunction "PWRON_51") (pintype "passive"))
    )
    (net (code "7") (name "Net-(Q3-G)") (class "Default")
      (node (ref "Q3") (pin "1") (pinfunction "G_1") (pintype "passive"))
      (node (ref "Q4") (pin "3") (pinfunction "D_3") (pintype "passive"))
      (node (ref "R89") (pin "2") (pinfunction "2_2") (pintype "passive"))
    )
    (net (code "8") (name "Net-(U14-OSC32KIN)") (class "Default")
      (node (ref "C282") (pin "1") (pinfunction "1_1") (pintype "passive"))
      (node (ref "U14") (pin "65") (pinfunction "OSC32KIN_65") (pintype "passive"))
      (node (ref "Y3") (pin "2") (pinfunction "2_2") (pintype "passive"))
    )
    (net (code "9") (name "Net-(U14-OSC32KOUT)") (class "Default")
      (node (ref "R81") (pin "1") (pinfunction "1_1") (pintype "passive"))
      (node (ref "U14") (pin "66") (pinfunction "OSC32KOUT_66") (pintype "passive"))
    )
    (net (code "10") (name "Net-(U14-SW1)") (class "Default")
      (node (ref "L6") (pin "2") (pinfunction "2_2") (pintype "passive"))
      (node (ref "U14") (pin "42") (pinfunction "SW5_42") (pintype "passive"))
      (node (ref "U14") (pin "43") (pinfunction "SW1_43") (pintype "passive"))
    )
    (net (code "11") (name "Net-(U14-SW2)") (class "Default")
      (node (ref "L8") (pin "2") (pinfunction "2_2") (pintype "passive"))
      (node (ref "U14") (pin "25") (pinfunction "SW6_25") (pintype "passive"))
      (node (ref "U14") (pin "26") (pinfunction "SW2_26") (pintype "passive"))
    )
    (net (code "12") (name "Net-(U14-SW3)") (class "Default")
      (node (ref "L7") (pin "1") (pinfunction "1_1") (pintype "passive"))
      (node (ref "U14") (pin "58") (pinfunction "SW3_58") (pintype "passive"))
    )
    (net (code "13") (name "Net-(U14-SW4)") (class "Default")
      (node (ref "L5") (pin "1") (pinfunction "1_1") (pintype "passive"))
      (node (ref "U14") (pin "61") (pinfunction "SW4_61") (pintype "passive"))
    )
    (net (code "14") (name "Net-(U14-VDC)") (class "Default")
      (node (ref "R85") (pin "1") (pinfunction "1_1") (pintype "passive"))
      (node (ref "R87") (pin "1") (pinfunction "1_1") (pintype "passive"))
      (node (ref "R88") (pin "2") (pinfunction "2_2") (pintype "passive"))
      (node (ref "U14") (pin "34") (pinfunction "VDC_34") (pintype "passive"))
    )
    (net (code "15") (name "Net-(U14-VFB3)") (class "Default")
      (node (ref "C268") (pin "1") (pinfunction "1_1") (pintype "passive"))
      (node (ref "R79") (pin "1") (pinfunction "1_1") (pintype "passive"))
      (node (ref "R80") (pin "2") (pinfunction "2_2") (pintype "passive"))
      (node (ref "U14") (pin "56") (pinfunction "VFB3_56") (pintype "passive"))
    )
    (net (code "16") (name "Net-(U14-VREF)") (class "Default")
      (node (ref "C272") (pin "2") (pinfunction "2_2") (pintype "passive"))
      (node (ref "U14") (pin "37") (pinfunction "VREF_37") (pintype "passive"))
    )
    (net (code "17") (name "PMIC_EXT_EN") (class "Default")
      (node (ref "U14") (pin "55") (pinfunction "EXT_EN_55") (pintype "passive"))
    )
    (net (code "18") (name "PMIC_INT_L") (class "Default")
      (node (ref "C297") (pin "2") (pinfunction "2_2") (pintype "passive"))
      (node (ref "U14") (pin "49") (pinfunction "INT_49") (pintype "passive"))
    )
    (net (code "19") (name "PMIC_SLEEP_H") (class "Default")
      (node (ref "C298") (pin "2") (pinfunction "2_2") (pintype "passive"))
      (node (ref "Q4") (pin "1") (pinfunction "G_1") (pintype "passive"))
      (node (ref "U14") (pin "50") (pinfunction "SLEEP_50") (pintype "passive"))
    )
    (net (code "20") (name "PWR_KEY") (class "Default")
      (node (ref "R86") (pin "1") (pinfunction "1_1") (pintype "passive"))
    )
    (net (code "21") (name "PWR_KEY_L") (class "Default")
      (node (ref "D5") (pin "A") (pinfunction "ANODE_A") (pintype "passive"))
    )
    (net (code "22") (name "RESET_IN_H") (class "Default")
      (node (ref "C296") (pin "2") (pinfunction "2_2") (pintype "passive"))
      (node (ref "U14") (pin "6") (pinfunction "ResetKey/VPPOTP_6") (pintype "passive"))
    )
    (net (code "23") (name "RESET_L") (class "Default")
      (node (ref "R84") (pin "1") (pinfunction "1_1") (pintype "passive"))
      (node (ref "U14") (pin "20") (pinfunction "NRESPWRON_20") (pintype "passive"))
    )
    (net (code "24") (name "RTC_BATT_IN") (class "Default")
      (node (ref "D4") (pin "A1") (pinfunction "A1_A1") (pintype "passive"))
    )
    (net (code "25") (name "RTC_CLKO_SOC") (class "Default")
      (node (ref "R82") (pin "1") (pinfunction "1_1") (pintype "passive"))
      (node (ref "U14") (pin "68") (pinfunction "CLK32KOUT1_68") (pintype "passive"))
    )
    (net (code "26") (name "VCC1V8_CAM") (class "Default")
      (node (ref "C284") (pin "2") (pinfunction "2_2") (pintype "passive"))
      (node (ref "U14") (pin "31") (pinfunction "VLDO1_31") (pintype "passive"))
    )
    (net (code "27") (name "VCC1V8_PMUPLL") (class "Default")
      (node (ref "C286") (pin "2") (pinfunction "2_2") (pintype "passive"))
      (node (ref "U14") (pin "3") (pinfunction "VLDO3_3") (pintype "passive"))
    )
    (net (code "28") (name "VCC3V0_TOUCH") (class "Default")
      (node (ref "C285") (pin "2") (pinfunction "2_2") (pintype "passive"))
      (node (ref "U14") (pin "33") (pinfunction "VLDO2_33") (pintype "passive"))
    )
    (net (code "29") (name "VCC3V3_S0") (class "Default")
      (node (ref "C293") (pin "2") (pinfunction "2_2") (pintype "passive"))
      (node (ref "U14") (pin "11") (pinfunction "VSWOUT2_11") (pintype "passive"))
    )
    (net (code "30") (name "VCC3V3_S3") (class "Default")
      (node (ref "C292") (pin "2") (pinfunction "2_2") (pintype "passive"))
      (node (ref "U14") (pin "7") (pinfunction "VSWOUT1_7") (pintype "passive"))
    )
    (net (code "31") (name "VCC3V3_S5") (class "Default")
      (node (ref "C279") (pin "2") (pinfunction "2_2") (pintype "passive"))
      (node (ref "C280") (pin "2") (pinfunction "2_2") (pintype "passive"))
      (node (ref "D4") (pin "A2") (pinfunction "A2_A2") (pintype "passive"))
      (node (ref "R83") (pin "2") (pinfunction "2_2") (pintype "passive"))
      (node (ref "U14") (pin "35") (pinfunction "VLDOA_35") (pintype "passive"))
      (node (ref "U14") (pin "36") (pinfunction "VCCA_36") (pintype "passive"))
      (node (ref "U14") (pin "52") (pinfunction "BOOT0_52") (pintype "passive"))
      (node (ref "U14") (pin "53") (pinfunction "BOOT1_53") (pintype "passive"))
    )
    (net (code "32") (name "VCC3V3_SYS") (class "Default")
      (node (ref "C259") (pin "2") (pinfunction "2_2") (pintype "passive"))
      (node (ref "C260") (pin "2") (pinfunction "2_2") (pintype "passive"))
      (node (ref "C261") (pin "2") (pinfunction "2_2") (pintype "passive"))
      (node (ref "C262") (pin "2") (pinfunction "2_2") (pintype "passive"))
      (node (ref "C263") (pin "2") (pinfunction "2_2") (pintype "passive"))
      (node (ref "C264") (pin "2") (pinfunction "2_2") (pintype "passive"))
      (node (ref "C273") (pin "1") (pinfunction "1_1") (pintype "passive"))
      (node (ref "C274") (pin "2") (pinfunction "2_2") (pintype "passive"))
      (node (ref "C275") (pin "2") (pinfunction "2_2") (pintype "passive"))
      (node (ref "C276") (pin "2") (pinfunction "2_2") (pintype "passive"))
      (node (ref "C277") (pin "2") (pinfunction "2_2") (pintype "passive"))
      (node (ref "C278") (pin "2") (pinfunction "2_2") (pintype "passive"))
      (node (ref "R89") (pin "1") (pinfunction "1_1") (pintype "passive"))
      (node (ref "U14") (pin "1") (pinfunction "VCC10_1") (pintype "passive"))
      (node (ref "U14") (pin "10") (pinfunction "VCC12_10") (pintype "passive"))
      (node (ref "U14") (pin "13") (pinfunction "VCC9_13") (pintype "passive"))
      (node (ref "U14") (pin "16") (pinfunction "VCC11_16") (pintype "passive"))
      (node (ref "U14") (pin "23") (pinfunction "VCC14_23") (pintype "passive"))
      (node (ref "U14") (pin "24") (pinfunction "VCC2_24") (pintype "passive"))
      (node (ref "U14") (pin "32") (pinfunction "VCC6_32") (pintype "passive"))
      (node (ref "U14") (pin "4") (pinfunction "VCC7_4") (pintype "passive"))
      (node (ref "U14") (pin "44") (pinfunction "VCC13_44") (pintype "passive"))
      (node (ref "U14") (pin "45") (pinfunction "VCC1_45") (pintype "passive"))
      (node (ref "U14") (pin "59") (pinfunction "VCC3_59") (pintype "passive"))
      (node (ref "U14") (pin "60") (pinfunction "VCC4_60") (pintype "passive"))
      (node (ref "U14") (pin "8") (pinfunction "VCC8_8") (pintype "passive"))
    )
    (net (code "33") (name "VCCA1V8_CODEC") (class "Default")
      (node (ref "C287") (pin "2") (pinfunction "2_2") (pintype "passive"))
      (node (ref "U14") (pin "5") (pinfunction "VLDO7_5") (pintype "passive"))
    )
    (net (code "34") (name "VCCA3V0_CODEC") (class "Default")
      (node (ref "C289") (pin "2") (pinfunction "2_2") (pintype "passive"))
      (node (ref "U14") (pin "14") (pinfunction "VLDO5_14") (pintype "passive"))
    )
    (net (code "35") (name "VCC_1V5") (class "Default")
      (node (ref "C290") (pin "2") (pinfunction "2_2") (pintype "passive"))
      (node (ref "U14") (pin "2") (pinfunction "VLDO6_2") (pintype "passive"))
    )
    (net (code "36") (name "VCC_1V8") (class "Default")
      (node (ref "C265") (pin "2") (pinfunction "2_2") (pintype "passive"))
      (node (ref "L5") (pin "2") (pinfunction "2_2") (pintype "passive"))
      (node (ref "R82") (pin "2") (pinfunction "2_2") (pintype "passive"))
      (node (ref "R84") (pin "2") (pinfunction "2_2") (pintype "passive"))
      (node (ref "U14") (pin "63") (pinfunction "VFB4_63") (pintype "passive"))
    )
    (net (code "37") (name "VCC_3V0") (class "Default")
      (node (ref "C281") (pin "2") (pinfunction "2_2") (pintype "passive"))
      (node (ref "C291") (pin "2") (pinfunction "2_2") (pintype "passive"))
      (node (ref "U14") (pin "15") (pinfunction "VLDO8_15") (pintype "passive"))
      (node (ref "U14") (pin "17") (pinfunction "VDDIO_17") (pintype "passive"))
    )
    (net (code "38") (name "VCC_DDR") (class "Default")
      (node (ref "C268") (pin "2") (pinfunction "2_2") (pintype "passive"))
      (node (ref "C269") (pin "2") (pinfunction "2_2") (pintype "passive"))
      (node (ref "L7") (pin "2") (pinfunction "2_2") (pintype "passive"))
      (node (ref "Q3") (pin "3") (pinfunction "D_3") (pintype "passive"))
      (node (ref "R79") (pin "2") (pinfunction "2_2") (pintype "passive"))
    )
    (net (code "39") (name "VCC_DDRC") (class "Default")
      (node (ref "C300") (pin "2") (pinfunction "2_2") (pintype "passive"))
      (node (ref "Q3") (pin "2") (pinfunction "S_2") (pintype "passive"))
    )
    (net (code "40") (name "VCC_IN_CONN") (class "Default")
      (node (ref "C299") (pin "1") (pinfunction "1_1") (pintype "passive"))
    )
    (net (code "41") (name "VCC_RTC") (class "Default")
      (node (ref "C283") (pin "2") (pinfunction "2_2") (pintype "passive"))
      (node (ref "D4") (pin "K") (pinfunction "K_K") (pintype "passive"))
      (node (ref "U14") (pin "9") (pinfunction "VCCRTC_9") (pintype "passive"))
    )
    (net (code "42") (name "VCC_SDIO") (class "Default")
      (node (ref "C288") (pin "2") (pinfunction "2_2") (pintype "passive"))
      (node (ref "U14") (pin "12") (pinfunction "VLDO4_12") (pintype "passive"))
    )
    (net (code "43") (name "VDC_ONOFF") (class "Default")
      (node (ref "R85") (pin "2") (pinfunction "2_2") (pintype "passive"))
    )
    (net (code "44") (name "VDD_CENTER") (class "Default")
      (node (ref "C266") (pin "2") (pinfunction "2_2") (pintype "passive"))
      (node (ref "C267") (pin "2") (pinfunction "2_2") (pintype "passive"))
      (node (ref "L6") (pin "1") (pinfunction "1_1") (pintype "passive"))
      (node (ref "U14") (pin "39") (pinfunction "VFB1_39") (pintype "passive"))
    )
    (net (code "45") (name "VDD_CPU_L") (class "Default")
      (node (ref "C270") (pin "2") (pinfunction "2_2") (pintype "passive"))
      (node (ref "C271") (pin "2") (pinfunction "2_2") (pintype "passive"))
      (node (ref "L8") (pin "1") (pinfunction "1_1") (pintype "passive"))
      (node (ref "U14") (pin "29") (pinfunction "VFB2_29") (pintype "passive"))
    )
    (net (code "46") (name "unconnected-(U14-CLK32KOUT2-Pad67)") (class "Default")
      (node (ref "U14") (pin "67") (pinfunction "CLK32KOUT2_67") (pintype "passive+no_connect"))
    )
    (net (code "47") (name "unconnected-(U14-DVSOK-Pad54)") (class "Default")
      (node (ref "U14") (pin "54") (pinfunction "DVSOK_54") (pintype "passive+no_connect"))
    )
    (net (code "48") (name "unconnected-(U14-NC1-Pad47)") (class "Default")
      (node (ref "U14") (pin "47") (pinfunction "NC1_47") (pintype "passive+no_connect"))
    )
    (net (code "49") (name "unconnected-(U14-NC2-Pad48)") (class "Default")
      (node (ref "U14") (pin "48") (pinfunction "NC2_48") (pintype "passive+no_connect"))
    )
  )
)
